# clvHd.net
KiCad netlist of a schematic drawn in EAGLE
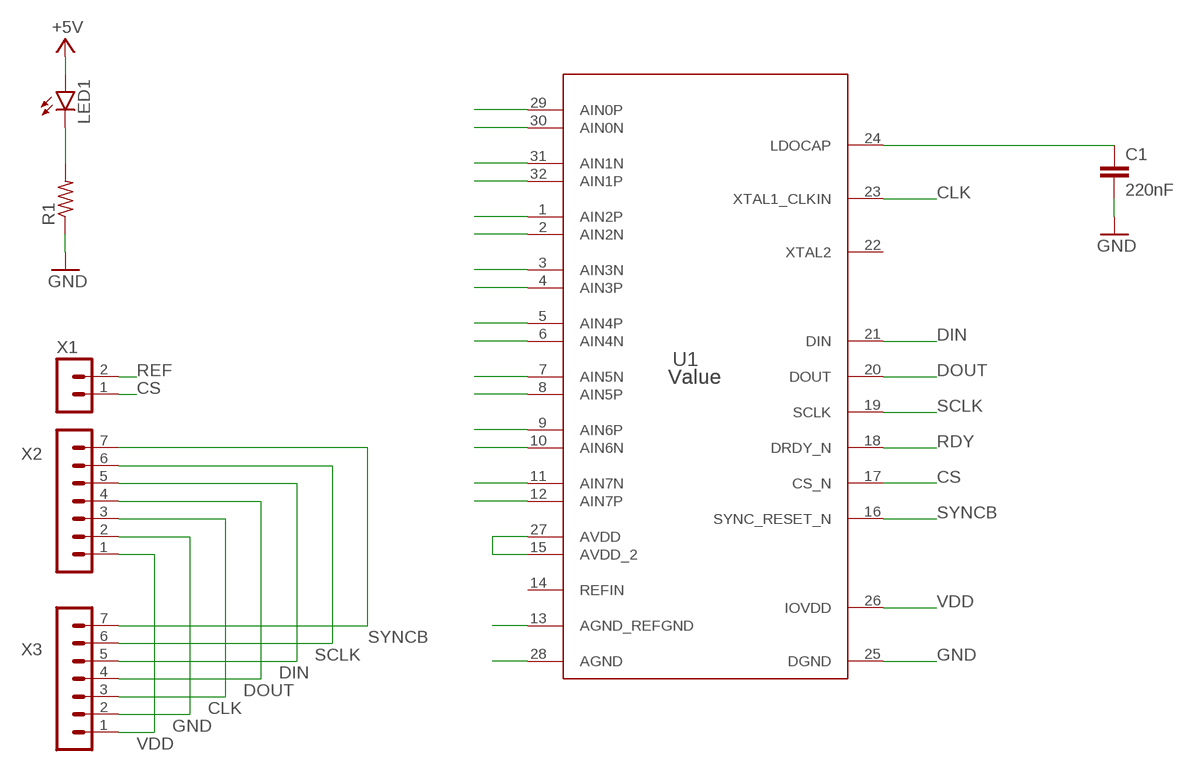
[diagram p0: schematic, sheet 1]

(export (version "E")
  (design (tool "Eeschema 10.0.6"))
  (components
    (comp (ref "C1")
      (value "220nF")
      (footprint "eagle-import:C0402")
      (libsource (lib "eagle-import") (part "C-EUC0402"))
    )
    (comp (ref "LED1")
      (value "LEDCHIP-LED0603")
      (footprint "eagle-import:CHIP-LED0603")
      (libsource (lib "eagle-import") (part "LEDCHIP-LED0603"))
    )
    (comp (ref "R1")
      (value "R-US_R0402")
      (footprint "eagle-import:R0402")
      (libsource (lib "eagle-import") (part "R-US_R0402"))
    )
    (comp (ref "U1")
      (value "Value")
      (footprint "eagle-import:PBS0032A_N")
      (fields (field (name "MANUFACTURER") "Texas Instruments") (field (name "PARTNUMBER") "ADS131M08IPBSR"))
      (libsource (lib "eagle-import") (part "ADS131M08IPBS"))
    )
    (comp (ref "X1")
      (value "BM02B-SRSS-TB")
      (footprint "eagle-import:BM02B-SRSS-TB")
      (libsource (lib "eagle-import") (part "BM02B-SRSS-TB"))
    )
    (comp (ref "X2")
      (value "BM07B-SRSS-TB")
      (footprint "eagle-import:BM07B-SRSS-TB")
      (libsource (lib "eagle-import") (part "BM07B-SRSS-TB"))
    )
    (comp (ref "X3")
      (value "BM07B-SRSS-TB")
      (footprint "eagle-import:BM07B-SRSS-TB")
      (libsource (lib "eagle-import") (part "BM07B-SRSS-TB"))
    )
  )
  (nets
    (net (code "1") (name "+5V") (class "Default")
      (node (ref "LED1") (pin "A") (pinfunction "A_A") (pintype "passive"))
    )
    (net (code "2") (name "/CLK") (class "Default")
      (node (ref "U1") (pin "23") (pinfunction "XTAL1_CLKIN_23") (pintype "input"))
      (node (ref "X2") (pin "3") (pinfunction "3_3") (pintype "passive"))
      (node (ref "X3") (pin "3") (pinfunction "3_3") (pintype "passive"))
    )
    (net (code "3") (name "/CS") (class "Default")
      (node (ref "U1") (pin "17") (pinfunction "CS_N_17") (pintype "input"))
      (node (ref "X1") (pin "1") (pinfunction "1_1") (pintype "passive"))
    )
    (net (code "4") (name "/DIN") (class "Default")
      (node (ref "U1") (pin "21") (pinfunction "DIN_21") (pintype "input"))
      (node (ref "X2") (pin "5") (pinfunction "5_5") (pintype "passive"))
      (node (ref "X3") (pin "5") (pinfunction "5_5") (pintype "passive"))
    )
    (net (code "5") (name "/DOUT") (class "Default")
      (node (ref "U1") (pin "20") (pinfunction "DOUT_20") (pintype "output"))
      (node (ref "X2") (pin "4") (pinfunction "4_4") (pintype "passive"))
      (node (ref "X3") (pin "4") (pinfunction "4_4") (pintype "passive"))
    )
    (net (code "6") (name "/RDY") (class "Default")
      (node (ref "U1") (pin "18") (pinfunction "DRDY_N_18") (pintype "output"))
    )
    (net (code "7") (name "/REF") (class "Default")
      (node (ref "X1") (pin "2") (pinfunction "2_2") (pintype "passive"))
    )
    (net (code "8") (name "/SCLK") (class "Default")
      (node (ref "U1") (pin "19") (pinfunction "SCLK_19") (pintype "input"))
      (node (ref "X2") (pin "6") (pinfunction "6_6") (pintype "passive"))
      (node (ref "X3") (pin "6") (pinfunction "6_6") (pintype "passive"))
    )
    (net (code "9") (name "/SYNCB") (class "Default")
      (node (ref "U1") (pin "16") (pinfunction "SYNC_RESET_N_16") (pintype "input"))
      (node (ref "X2") (pin "7") (pinfunction "7_7") (pintype "passive"))
      (node (ref "X3") (pin "7") (pinfunction "7_7") (pintype "passive"))
    )
    (net (code "10") (name "/VDD") (class "Default")
      (node (ref "U1") (pin "26") (pinfunction "IOVDD_26") (pintype "power_in"))
      (node (ref "X2") (pin "1") (pinfunction "1_1") (pintype "passive"))
      (node (ref "X3") (pin "1") (pinfunction "1_1") (pintype "passive"))
    )
    (net (code "11") (name "GND") (class "Default")
      (node (ref "C1") (pin "2") (pinfunction "2_2") (pintype "passive"))
      (node (ref "R1") (pin "1") (pinfunction "1_1") (pintype "passive"))
      (node (ref "U1") (pin "25") (pinfunction "DGND_25") (pintype "power_in"))
      (node (ref "X2") (pin "2") (pinfunction "2_2") (pintype "passive"))
      (node (ref "X3") (pin "2") (pinfunction "2_2") (pintype "passive"))
    )
    (net (code "12") (name "Net-(LED1-PadC)") (class "Default")
      (node (ref "LED1") (pin "C") (pinfunction "C_C") (pintype "passive"))
      (node (ref "R1") (pin "2") (pinfunction "2_2") (pintype "passive"))
    )
    (net (code "13") (name "Net-(U1-AVDD)") (class "Default")
      (node (ref "U1") (pin "15") (pinfunction "AVDD_2_15") (pintype "power_in"))
      (node (ref "U1") (pin "27") (pinfunction "AVDD_27") (pintype "power_in"))
    )
    (net (code "14") (name "Net-(U1-LDOCAP)") (class "Default")
      (node (ref "C1") (pin "1") (pinfunction "1_1") (pintype "passive"))
      (node (ref "U1") (pin "24") (pinfunction "LDOCAP_24") (pintype "passive"))
    )
    (net (code "15") (name "unconnected-(U1-AGND-Pad28)") (class "Default")
      (node (ref "U1") (pin "28") (pinfunction "AGND_28") (pintype "power_in"))
    )
    (net (code "16") (name "unconnected-(U1-AGND_REFGND-Pad13)") (class "Default")
      (node (ref "U1") (pin "13") (pinfunction "AGND_REFGND_13") (pintype "power_in"))
    )
    (net (code "17") (name "unconnected-(U1-AIN0N-Pad30)") (class "Default")
      (node (ref "U1") (pin "30") (pinfunction "AIN0N_30") (pintype "input"))
    )
    (net (code "18") (name "unconnected-(U1-AIN0P-Pad29)") (class "Default")
      (node (ref "U1") (pin "29") (pinfunction "AIN0P_29") (pintype "input"))
    )
    (net (code "19") (name "unconnected-(U1-AIN1N-Pad31)") (class "Default")
      (node (ref "U1") (pin "31") (pinfunction "AIN1N_31") (pintype "input"))
    )
    (net (code "20") (name "unconnected-(U1-AIN1P-Pad32)") (class "Default")
      (node (ref "U1") (pin "32") (pinfunction "AIN1P_32") (pintype "input"))
    )
    (net (code "21") (name "unconnected-(U1-AIN2N-Pad2)") (class "Default")
      (node (ref "U1") (pin "2") (pinfunction "AIN2N_2") (pintype "input"))
    )
    (net (code "22") (name "unconnected-(U1-AIN2P-Pad1)") (class "Default")
      (node (ref "U1") (pin "1") (pinfunction "AIN2P_1") (pintype "input"))
    )
    (net (code "23") (name "unconnected-(U1-AIN3N-Pad3)") (class "Default")
      (node (ref "U1") (pin "3") (pinfunction "AIN3N_3") (pintype "input"))
    )
    (net (code "24") (name "unconnected-(U1-AIN3P-Pad4)") (class "Default")
      (node (ref "U1") (pin "4") (pinfunction "AIN3P_4") (pintype "input"))
    )
    (net (code "25") (name "unconnected-(U1-AIN4N-Pad6)") (class "Default")
      (node (ref "U1") (pin "6") (pinfunction "AIN4N_6") (pintype "input"))
    )
    (net (code "26") (name "unconnected-(U1-AIN4P-Pad5)") (class "Default")
      (node (ref "U1") (pin "5") (pinfunction "AIN4P_5") (pintype "input"))
    )
    (net (code "27") (name "unconnected-(U1-AIN5N-Pad7)") (class "Default")
      (node (ref "U1") (pin "7") (pinfunction "AIN5N_7") (pintype "input"))
    )
    (net (code "28") (name "unconnected-(U1-AIN5P-Pad8)") (class "Default")
      (node (ref "U1") (pin "8") (pinfunction "AIN5P_8") (pintype "input"))
    )
    (net (code "29") (name "unconnected-(U1-AIN6N-Pad10)") (class "Default")
      (node (ref "U1") (pin "10") (pinfunction "AIN6N_10") (pintype "input"))
    )
    (net (code "30") (name "unconnected-(U1-AIN6P-Pad9)") (class "Default")
      (node (ref "U1") (pin "9") (pinfunction "AIN6P_9") (pintype "input"))
    )
    (net (code "31") (name "unconnected-(U1-AIN7N-Pad11)") (class "Default")
      (node (ref "U1") (pin "11") (pinfunction "AIN7N_11") (pintype "input"))
    )
    (net (code "32") (name "unconnected-(U1-AIN7P-Pad12)") (class "Default")
      (node (ref "U1") (pin "12") (pinfunction "AIN7P_12") (pintype "input"))
    )
    (net (code "33") (name "unconnected-(U1-REFIN-Pad14)") (class "Default")
      (node (ref "U1") (pin "14") (pinfunction "REFIN_14") (pintype "input"))
    )
    (net (code "34") (name "unconnected-(U1-XTAL2-Pad22)") (class "Default")
      (node (ref "U1") (pin "22") (pinfunction "XTAL2_22") (pintype "input"))
    )
  )
)
